# SDMMC_EMMC_PCIE_ADC_Blocks.net
KiCad netlist of a schematic drawn in Altium Designer
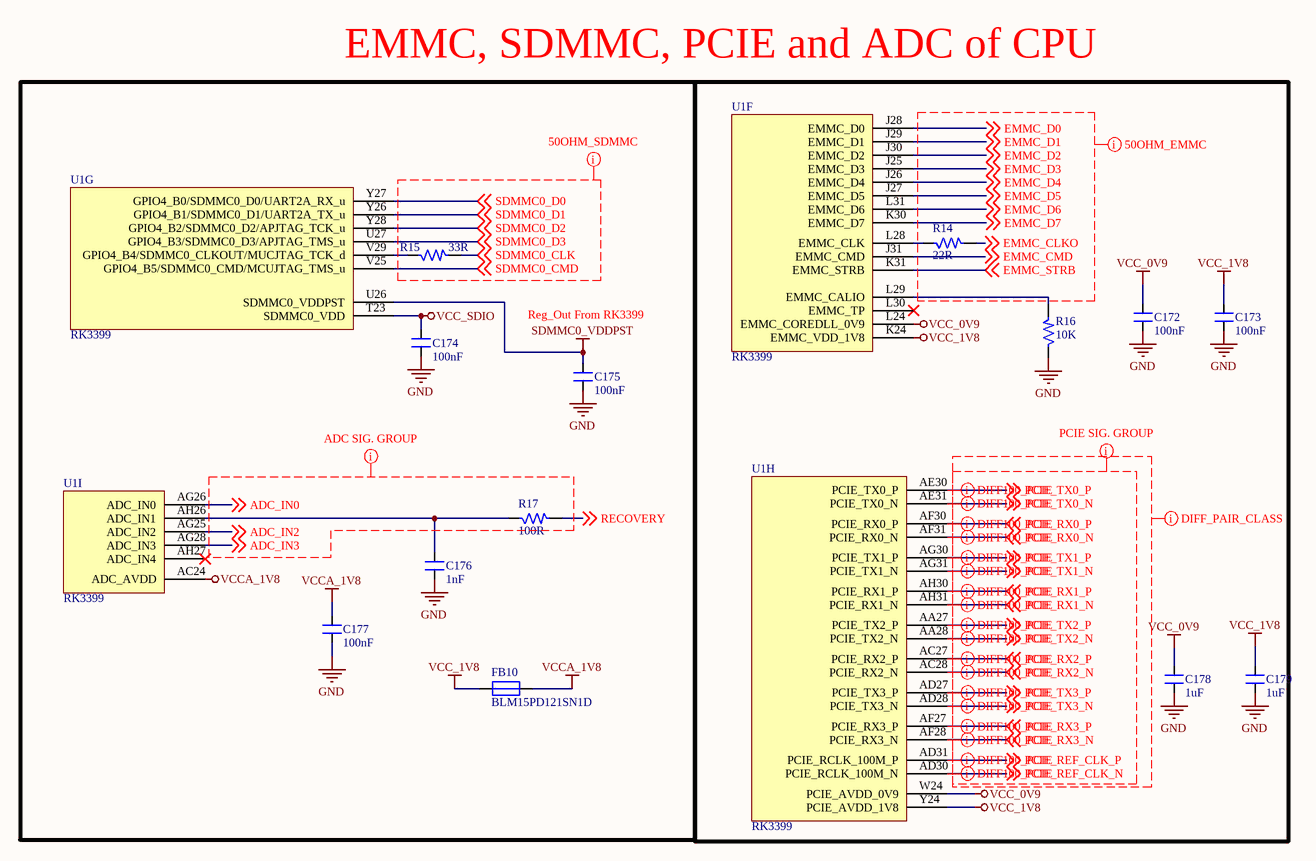
[diagram p0: SDMMC EMMC PCIE ADC Blocks.SchDoc]

(export (version "E")
  (design (tool "Eeschema 10.0.6"))
  (components
    (comp (ref "C172")
      (value "100nF")
      (footprint "CAP_0201")
      (description "0.1µF ±10% 25V Ceramic Capacitor X5R 0201 (0603 Metric)")
      (fields
        (field (name "MANUFACTURER") "TDK Corporation")
        (field (name "MANUFACTURER PART NUMBER") "C0603X5R1E104K030BB")
      )
      (libsource (lib "RK3399 _Module_Intlib") (part "CAP_100nF-25V-10%-0201"))
    )
    (comp (ref "C173")
      (value "100nF")
      (footprint "CAP_0201")
      (description "0.1µF ±10% 25V Ceramic Capacitor X5R 0201 (0603 Metric)")
      (fields
        (field (name "MANUFACTURER") "TDK Corporation")
        (field (name "MANUFACTURER PART NUMBER") "C0603X5R1E104K030BB")
      )
      (libsource (lib "RK3399 _Module_Intlib") (part "CAP_100nF-25V-10%-0201"))
    )
    (comp (ref "C174")
      (value "100nF")
      (footprint "CAP_0201")
      (description "0.1µF ±10% 25V Ceramic Capacitor X5R 0201 (0603 Metric)")
      (fields
        (field (name "MANUFACTURER") "TDK Corporation")
        (field (name "MANUFACTURER PART NUMBER") "C0603X5R1E104K030BB")
      )
      (libsource (lib "RK3399 _Module_Intlib") (part "CAP_100nF-25V-10%-0201"))
    )
    (comp (ref "C175")
      (value "100nF")
      (footprint "CAP_0201")
      (description "0.1µF ±10% 25V Ceramic Capacitor X5R 0201 (0603 Metric)")
      (fields
        (field (name "MANUFACTURER") "TDK Corporation")
        (field (name "MANUFACTURER PART NUMBER") "C0603X5R1E104K030BB")
      )
      (libsource (lib "RK3399 _Module_Intlib") (part "CAP_100nF-25V-10%-0201"))
    )
    (comp (ref "C176")
      (value "1nF")
      (footprint "CAP_0201")
      (description "1000pF ±10% 16V Ceramic Capacitor X7R 0201 (0603 Metric)")
      (fields
        (field (name "MANUFACTURER") "Murata Electronics")
        (field (name "MANUFACTURER PART NUMBER") "GRM033R71C102KA01D")
      )
      (libsource (lib "RK3399 _Module_Intlib") (part "CAP_1nF-16V-10%-0201"))
    )
    (comp (ref "C177")
      (value "100nF")
      (footprint "CAP_0201")
      (description "0.1µF ±10% 25V Ceramic Capacitor X5R 0201 (0603 Metric)")
      (fields
        (field (name "MANUFACTURER") "TDK Corporation")
        (field (name "MANUFACTURER PART NUMBER") "C0603X5R1E104K030BB")
      )
      (libsource (lib "RK3399 _Module_Intlib") (part "CAP_100nF-25V-10%-0201"))
    )
    (comp (ref "C178")
      (value "1uF")
      (footprint "CAP_0201")
      (description "1µF ±20% 16V Ceramic Capacitor X5R 0201 (0603 Metric)")
      (fields
        (field (name "MANUFACTURER") "Samsung Electro-Mechanics")
        (field (name "MANUFACTURER PART NUMBER") "CL03A105MO3NRNH")
      )
      (libsource (lib "RK3399 _Module_Intlib") (part "CAP_1uF-16V-10%-0201"))
    )
    (comp (ref "C179")
      (value "1uF")
      (footprint "CAP_0201")
      (description "1µF ±20% 16V Ceramic Capacitor X5R 0201 (0603 Metric)")
      (fields
        (field (name "MANUFACTURER") "Samsung Electro-Mechanics")
        (field (name "MANUFACTURER PART NUMBER") "CL03A105MO3NRNH")
      )
      (libsource (lib "RK3399 _Module_Intlib") (part "CAP_1uF-16V-10%-0201"))
    )
    (comp (ref "FB10")
      (value "BLM15PD121SN1D")
      (footprint "RES_0402")
      (description "120 Ohms @ 100MHz 1 Power Line Ferrite Bead 0402 (1005 Metric) 1.3A 90mOhm")
      (fields (field (name "MANUFACTURER") "Murata Electronics"))
      (libsource (lib "RK3399 _Module_Schlib") (part "FB_120R-1.3A-100Mhz-0402"))
    )
    (comp (ref "R14")
      (value "22R")
      (footprint "RES_0201")
      (description "22 Ohms ±1% 0.05W, 1/20W Chip Resistor 0201 (0603 Metric) Moisture Resistant Thick Film")
      (fields
        (field (name "MANUFACTURER") "Yageo")
        (field (name "MANUFACTURER PART NUMBER") "RC0201FR-0722RL")
      )
      (libsource (lib "EsteemPCB_SOM_Course_schlib") (part "RES_22R-0.05W-1%-0201"))
    )
    (comp (ref "R15")
      (value "33R")
      (footprint "RES_0201")
      (description "33 Ohms ±1% 0.05W, 1/20W Chip Resistor 0201 (0603 Metric) Thick Film")
      (fields
        (field (name "MANUFACTURER") "Yageo")
        (field (name "MANUFACTURER PART NUMBER") "RC0201FR-0733RL")
      )
      (libsource (lib "RK3399 _Module_Intlib") (part "RES_33R-0.05W-1%-0201"))
    )
    (comp (ref "R16")
      (value "10K")
      (footprint "RES_0201")
      (description "10 kOhms ±1% 0.05W, 1/20W Chip Resistor 0201 (0603 Metric) Thick Film")
      (fields
        (field (name "MANUFACTURER") "Stackpole Electronics Inc")
        (field (name "MANUFACTURER PART NUMBER") "RMCF0201FT10K0")
      )
      (libsource (lib "RK3399 _Module_Intlib") (part "RES_10K-0.05W-1%-0201"))
    )
    (comp (ref "R17")
      (value "100R")
      (footprint "RES_0201")
      (description "100 kOhms ±1% 0.05W, 1/20W Chip Resistor 0201 (0603 Metric) Automotive AEC-Q200 Thick Film")
      (fields
        (field (name "MANUFACTURER") "Panasonic Electronic Components")
        (field (name "MANUFACTURER PART NUMBER") "ERJ-1GNF1003C")
      )
      (libsource (lib "RK3399 _Module_Intlib") (part "RES_100R-0.05W-1%-0201"))
    )
    (comp (ref "U1")
      (value "RK3399")
      (footprint "FBGA828_23_826X826")
      (description "RK3399 is a low power, high performance processor for computing, personal mobile.")
      (fields (field (name "MANUFACTURER") "Rockchip"))
      (libsource (lib "RK3399 _Module_Schlib") (part "IC_RK3399-FCBGA828"))
    )
  )
  (nets
    (net (code "1") (name "ADC_IN0") (class "Default")
      (node (ref "U1") (pin "AG26") (pinfunction "ADC_IN0_AG26") (pintype "passive"))
    )
    (net (code "2") (name "ADC_IN2") (class "Default")
      (node (ref "U1") (pin "AG25") (pinfunction "ADC_IN2_AG25") (pintype "passive"))
    )
    (net (code "3") (name "ADC_IN3") (class "Default")
      (node (ref "U1") (pin "AG28") (pinfunction "ADC_IN3_AG28") (pintype "passive"))
    )
    (net (code "4") (name "EMMC_CLKO") (class "Default")
      (node (ref "R14") (pin "2") (pinfunction "2_2") (pintype "passive"))
    )
    (net (code "5") (name "EMMC_CMD") (class "Default")
      (node (ref "U1") (pin "J31") (pinfunction "EMMC_CMD_J31") (pintype "passive"))
    )
    (net (code "6") (name "EMMC_D0") (class "Default")
      (node (ref "U1") (pin "J28") (pinfunction "EMMC_D0_J28") (pintype "passive"))
    )
    (net (code "7") (name "EMMC_D1") (class "Default")
      (node (ref "U1") (pin "J29") (pinfunction "EMMC_D1_J29") (pintype "passive"))
    )
    (net (code "8") (name "EMMC_D2") (class "Default")
      (node (ref "U1") (pin "J30") (pinfunction "EMMC_D2_J30") (pintype "passive"))
    )
    (net (code "9") (name "EMMC_D3") (class "Default")
      (node (ref "U1") (pin "J25") (pinfunction "EMMC_D3_J25") (pintype "passive"))
    )
    (net (code "10") (name "EMMC_D4") (class "Default")
      (node (ref "U1") (pin "J26") (pinfunction "EMMC_D4_J26") (pintype "passive"))
    )
    (net (code "11") (name "EMMC_D5") (class "Default")
      (node (ref "U1") (pin "J27") (pinfunction "EMMC_D5_J27") (pintype "passive"))
    )
    (net (code "12") (name "EMMC_D6") (class "Default")
      (node (ref "U1") (pin "L31") (pinfunction "EMMC_D6_L31") (pintype "passive"))
    )
    (net (code "13") (name "EMMC_D7") (class "Default")
      (node (ref "U1") (pin "K30") (pinfunction "EMMC_D7_K30") (pintype "passive"))
    )
    (net (code "14") (name "EMMC_STRB") (class "Default")
      (node (ref "U1") (pin "K31") (pinfunction "EMMC_STRB_K31") (pintype "passive"))
    )
    (net (code "15") (name "GND") (class "Default")
      (node (ref "C172") (pin "1") (pinfunction "1_1") (pintype "passive"))
      (node (ref "C173") (pin "1") (pinfunction "1_1") (pintype "passive"))
      (node (ref "C174") (pin "1") (pinfunction "1_1") (pintype "passive"))
      (node (ref "C175") (pin "1") (pinfunction "1_1") (pintype "passive"))
      (node (ref "C176") (pin "1") (pinfunction "1_1") (pintype "passive"))
      (node (ref "C177") (pin "1") (pinfunction "1_1") (pintype "passive"))
      (node (ref "C178") (pin "1") (pinfunction "1_1") (pintype "passive"))
      (node (ref "C179") (pin "1") (pinfunction "1_1") (pintype "passive"))
      (node (ref "R16") (pin "1") (pinfunction "1_1") (pintype "passive"))
    )
    (net (code "16") (name "Net-(U1F-EMMC_CALIO)") (class "Default")
      (node (ref "R16") (pin "2") (pinfunction "2_2") (pintype "passive"))
      (node (ref "U1") (pin "L29") (pinfunction "EMMC_CALIO_L29") (pintype "passive"))
    )
    (net (code "17") (name "Net-(U1F-EMMC_CLK)") (class "Default")
      (node (ref "R14") (pin "1") (pinfunction "1_1") (pintype "passive"))
      (node (ref "U1") (pin "L28") (pinfunction "EMMC_CLK_L28") (pintype "passive"))
    )
    (net (code "18") (name "Net-(U1G-GPIO4_B4{slash}SDMMC0_CLKOUT{slash}MUCJTAG_TCK_d)") (class "Default")
      (node (ref "R15") (pin "1") (pinfunction "1_1") (pintype "passive"))
      (node (ref "U1") (pin "V29") (pinfunction "GPIO4_B4/SDMMC0_CLKOUT/MUCJTAG_TCK_d_V29") (pintype "passive"))
    )
    (net (code "19") (name "Net-(U1I-ADC_IN1)") (class "Default")
      (node (ref "C176") (pin "2") (pinfunction "2_2") (pintype "passive"))
      (node (ref "R17") (pin "1") (pinfunction "1_1") (pintype "passive"))
      (node (ref "U1") (pin "AH26") (pinfunction "ADC_IN1_AH26") (pintype "passive"))
    )
    (net (code "20") (name "PCIE_REF_CLK_N") (class "Default")
      (node (ref "U1") (pin "AD30") (pinfunction "PCIE_RCLK_100M_N_AD30") (pintype "passive"))
    )
    (net (code "21") (name "PCIE_REF_CLK_P") (class "Default")
      (node (ref "U1") (pin "AD31") (pinfunction "PCIE_RCLK_100M_P_AD31") (pintype "passive"))
    )
    (net (code "22") (name "PCIE_RX0_N") (class "Default")
      (node (ref "U1") (pin "AF31") (pinfunction "PCIE_RX0_N_AF31") (pintype "passive"))
    )
    (net (code "23") (name "PCIE_RX0_P") (class "Default")
      (node (ref "U1") (pin "AF30") (pinfunction "PCIE_RX0_P_AF30") (pintype "passive"))
    )
    (net (code "24") (name "PCIE_RX1_N") (class "Default")
      (node (ref "U1") (pin "AH31") (pinfunction "PCIE_RX1_N_AH31") (pintype "passive"))
    )
    (net (code "25") (name "PCIE_RX1_P") (class "Default")
      (node (ref "U1") (pin "AH30") (pinfunction "PCIE_RX1_P_AH30") (pintype "passive"))
    )
    (net (code "26") (name "PCIE_RX2_N") (class "Default")
      (node (ref "U1") (pin "AC28") (pinfunction "PCIE_RX2_N_AC28") (pintype "passive"))
    )
    (net (code "27") (name "PCIE_RX2_P") (class "Default")
      (node (ref "U1") (pin "AC27") (pinfunction "PCIE_RX2_P_AC27") (pintype "passive"))
    )
    (net (code "28") (name "PCIE_RX3_N") (class "Default")
      (node (ref "U1") (pin "AF28") (pinfunction "PCIE_RX3_N_AF28") (pintype "passive"))
    )
    (net (code "29") (name "PCIE_RX3_P") (class "Default")
      (node (ref "U1") (pin "AF27") (pinfunction "PCIE_RX3_P_AF27") (pintype "passive"))
    )
    (net (code "30") (name "PCIE_TX0_N") (class "Default")
      (node (ref "U1") (pin "AE31") (pinfunction "PCIE_TX0_N_AE31") (pintype "passive"))
    )
    (net (code "31") (name "PCIE_TX0_P") (class "Default")
      (node (ref "U1") (pin "AE30") (pinfunction "PCIE_TX0_P_AE30") (pintype "passive"))
    )
    (net (code "32") (name "PCIE_TX1_N") (class "Default")
      (node (ref "U1") (pin "AG31") (pinfunction "PCIE_TX1_N_AG31") (pintype "passive"))
    )
    (net (code "33") (name "PCIE_TX1_P") (class "Default")
      (node (ref "U1") (pin "AG30") (pinfunction "PCIE_TX1_P_AG30") (pintype "passive"))
    )
    (net (code "34") (name "PCIE_TX2_N") (class "Default")
      (node (ref "U1") (pin "AA28") (pinfunction "PCIE_TX2_N_AA28") (pintype "passive"))
    )
    (net (code "35") (name "PCIE_TX2_P") (class "Default")
      (node (ref "U1") (pin "AA27") (pinfunction "PCIE_TX2_P_AA27") (pintype "passive"))
    )
    (net (code "36") (name "PCIE_TX3_N") (class "Default")
      (node (ref "U1") (pin "AD28") (pinfunction "PCIE_TX3_N_AD28") (pintype "passive"))
    )
    (net (code "37") (name "PCIE_TX3_P") (class "Default")
      (node (ref "U1") (pin "AD27") (pinfunction "PCIE_TX3_P_AD27") (pintype "passive"))
    )
    (net (code "38") (name "RECOVERY") (class "Default")
      (node (ref "R17") (pin "2") (pinfunction "2_2") (pintype "passive"))
    )
    (net (code "39") (name "SDMMC0_CLK") (class "Default")
      (node (ref "R15") (pin "2") (pinfunction "2_2") (pintype "passive"))
    )
    (net (code "40") (name "SDMMC0_CMD") (class "Default")
      (node (ref "U1") (pin "V25") (pinfunction "GPIO4_B5/SDMMC0_CMD/MCUJTAG_TMS_u_V25") (pintype "passive"))
    )
    (net (code "41") (name "SDMMC0_D0") (class "Default")
      (node (ref "U1") (pin "Y27") (pinfunction "GPIO4_B0/SDMMC0_D0/UART2A_RX_u_Y27") (pintype "passive"))
    )
    (net (code "42") (name "SDMMC0_D1") (class "Default")
      (node (ref "U1") (pin "Y26") (pinfunction "GPIO4_B1/SDMMC0_D1/UART2A_TX_u_Y26") (pintype "passive"))
    )
    (net (code "43") (name "SDMMC0_D2") (class "Default")
      (node (ref "U1") (pin "Y28") (pinfunction "GPIO4_B2/SDMMC0_D2/APJTAG_TCK_u_Y28") (pintype "passive"))
    )
    (net (code "44") (name "SDMMC0_D3") (class "Default")
      (node (ref "U1") (pin "U27") (pinfunction "GPIO4_B3/SDMMC0_D3/APJTAG_TMS_u_U27") (pintype "passive"))
    )
    (net (code "45") (name "SDMMC0_VDDPST") (class "Default")
      (node (ref "C175") (pin "2") (pinfunction "2_2") (pintype "passive"))
      (node (ref "U1") (pin "U26") (pinfunction "SDMMC0_VDDPST_U26") (pintype "passive"))
    )
    (net (code "46") (name "VCCA_1V8") (class "Default")
      (node (ref "C177") (pin "2") (pinfunction "2_2") (pintype "passive"))
      (node (ref "FB10") (pin "2") (pinfunction "2_2") (pintype "passive"))
      (node (ref "U1") (pin "AC24") (pinfunction "ADC_AVDD_AC24") (pintype "passive"))
    )
    (net (code "47") (name "VCC_0V9") (class "Default")
      (node (ref "C172") (pin "2") (pinfunction "2_2") (pintype "passive"))
      (node (ref "C178") (pin "2") (pinfunction "2_2") (pintype "passive"))
      (node (ref "U1") (pin "L24") (pinfunction "EMMC_COREDLL_0V9_L24") (pintype "passive"))
      (node (ref "U1") (pin "W24") (pinfunction "PCIE_AVDD_0V9_W24") (pintype "passive"))
    )
    (net (code "48") (name "VCC_1V8") (class "Default")
      (node (ref "C173") (pin "2") (pinfunction "2_2") (pintype "passive"))
      (node (ref "C179") (pin "2") (pinfunction "2_2") (pintype "passive"))
      (node (ref "FB10") (pin "1") (pinfunction "1_1") (pintype "passive"))
      (node (ref "U1") (pin "K24") (pinfunction "EMMC_VDD_1V8_K24") (pintype "passive"))
      (node (ref "U1") (pin "Y24") (pinfunction "PCIE_AVDD_1V8_Y24") (pintype "passive"))
    )
    (net (code "49") (name "VCC_SDIO") (class "Default")
      (node (ref "C174") (pin "2") (pinfunction "2_2") (pintype "passive"))
      (node (ref "U1") (pin "T23") (pinfunction "SDMMC0_VDD_T23") (pintype "passive"))
    )
    (net (code "50") (name "unconnected-(U1F-EMMC_TP-PadL30)") (class "Default")
      (node (ref "U1") (pin "L30") (pinfunction "EMMC_TP_L30") (pintype "passive+no_connect"))
    )
    (net (code "51") (name "unconnected-(U1I-ADC_IN4-PadAH27)") (class "Default")
      (node (ref "U1") (pin "AH27") (pinfunction "ADC_IN4_AH27") (pintype "passive+no_connect"))
    )
  )
)
